# TXB0104_breakout.net
KiCad netlist of a schematic drawn in EAGLE
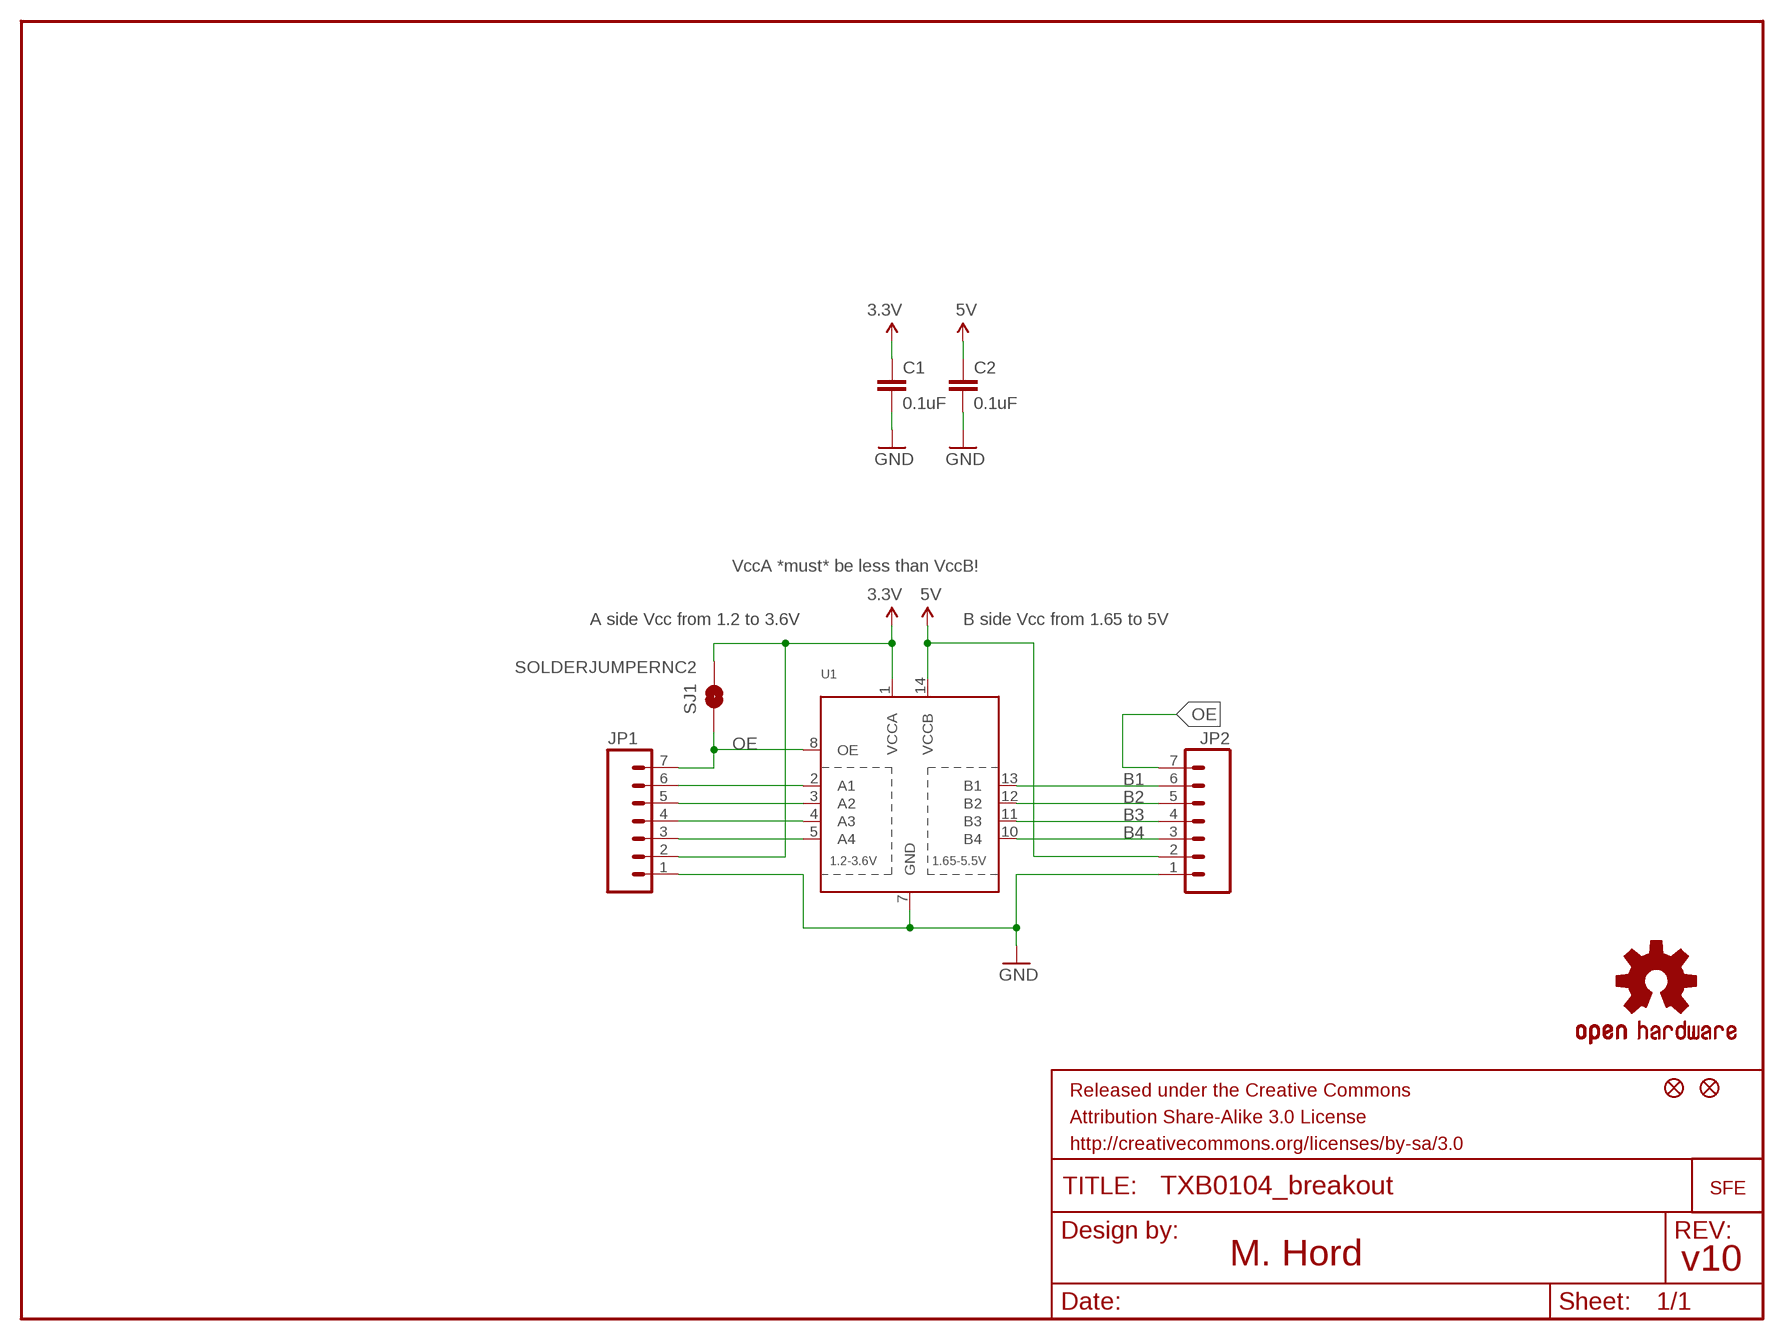
[diagram p0: schematic, sheet 1]

(export (version "E")
  (design (tool "Eeschema 10.0.6"))
  (components
    (comp (ref "C1")
      (value "0.1uF")
      (footprint "eagle-import:0603-CAP")
      (libsource (lib "eagle-import") (part "0.1UF-25V(+80/-20%)(0603)"))
    )
    (comp (ref "C2")
      (value "0.1uF")
      (footprint "eagle-import:0603-CAP")
      (libsource (lib "eagle-import") (part "0.1UF-25V(+80/-20%)(0603)"))
    )
    (comp (ref "FID1")
      (value "FIDUCIALUFIDUCIAL")
      (footprint "eagle-import:MICRO-FIDUCIAL")
      (libsource (lib "eagle-import") (part "FIDUCIALUFIDUCIAL"))
    )
    (comp (ref "FID2")
      (value "FIDUCIALUFIDUCIAL")
      (footprint "eagle-import:MICRO-FIDUCIAL")
      (libsource (lib "eagle-import") (part "FIDUCIALUFIDUCIAL"))
    )
    (comp (ref "FRAME1")
      (value "FRAME-LETTER")
      (footprint "eagle-import:CREATIVE_COMMONS")
      (libsource (lib "eagle-import") (part "FRAME-LETTER"))
    )
    (comp (ref "JP1")
      (value "M07")
      (footprint "eagle-import:1X07")
      (libsource (lib "eagle-import") (part "M07"))
    )
    (comp (ref "JP2")
      (value "M07")
      (footprint "eagle-import:1X07")
      (libsource (lib "eagle-import") (part "M07"))
    )
    (comp (ref "LOGO1")
      (value "LOGO-SFESK")
      (footprint "eagle-import:SFE-LOGO-FLAME")
      (libsource (lib "eagle-import") (part "LOGO-SFESK"))
    )
    (comp (ref "LOGO2")
      (value "OSHW-LOGOS")
      (footprint "eagle-import:OSHW-LOGO-S")
      (libsource (lib "eagle-import") (part "OSHW-LOGOS"))
    )
    (comp (ref "SJ1")
      (value "SOLDERJUMPERNC2")
      (footprint "eagle-import:SJ_2S-NOTRACE")
      (libsource (lib "eagle-import") (part "SOLDERJUMPERNC2"))
    )
    (comp (ref "U1")
      (value "TXB0104PWRSOIC14")
      (footprint "eagle-import:SO14")
      (libsource (lib "eagle-import") (part "TXB0104PWRSOIC14"))
    )
  )
  (nets
    (net (code "1") (name "/B1") (class "Default")
      (node (ref "JP2") (pin "6") (pinfunction "6_6") (pintype "passive"))
      (node (ref "U1") (pin "13") (pinfunction "B1_13") (pintype "bidirectional"))
    )
    (net (code "2") (name "/B2") (class "Default")
      (node (ref "JP2") (pin "5") (pinfunction "5_5") (pintype "passive"))
      (node (ref "U1") (pin "12") (pinfunction "B2_12") (pintype "bidirectional"))
    )
    (net (code "3") (name "/B3") (class "Default")
      (node (ref "JP2") (pin "4") (pinfunction "4_4") (pintype "passive"))
      (node (ref "U1") (pin "11") (pinfunction "B3_11") (pintype "bidirectional"))
    )
    (net (code "4") (name "/B4") (class "Default")
      (node (ref "JP2") (pin "3") (pinfunction "3_3") (pintype "passive"))
      (node (ref "U1") (pin "10") (pinfunction "B4_10") (pintype "bidirectional"))
    )
    (net (code "5") (name "3.3V") (class "Default")
      (node (ref "C1") (pin "1") (pinfunction "1_1") (pintype "passive"))
      (node (ref "JP1") (pin "2") (pinfunction "2_2") (pintype "passive"))
      (node (ref "SJ1") (pin "2") (pinfunction "2_2") (pintype "passive"))
      (node (ref "U1") (pin "1") (pinfunction "VCCA_1") (pintype "bidirectional"))
    )
    (net (code "6") (name "5V") (class "Default")
      (node (ref "C2") (pin "1") (pinfunction "1_1") (pintype "passive"))
      (node (ref "JP2") (pin "2") (pinfunction "2_2") (pintype "passive"))
      (node (ref "U1") (pin "14") (pinfunction "VCCB_14") (pintype "bidirectional"))
    )
    (net (code "7") (name "GND") (class "Default")
      (node (ref "C1") (pin "2") (pinfunction "2_2") (pintype "passive"))
      (node (ref "C2") (pin "2") (pinfunction "2_2") (pintype "passive"))
      (node (ref "JP1") (pin "1") (pinfunction "1_1") (pintype "passive"))
      (node (ref "JP2") (pin "1") (pinfunction "1_1") (pintype "passive"))
      (node (ref "U1") (pin "7") (pinfunction "GND_7") (pintype "bidirectional"))
    )
    (net (code "8") (name "Net-(U1-A1)") (class "Default")
      (node (ref "JP1") (pin "6") (pinfunction "6_6") (pintype "passive"))
      (node (ref "U1") (pin "2") (pinfunction "A1_2") (pintype "bidirectional"))
    )
    (net (code "9") (name "Net-(U1-A2)") (class "Default")
      (node (ref "JP1") (pin "5") (pinfunction "5_5") (pintype "passive"))
      (node (ref "U1") (pin "3") (pinfunction "A2_3") (pintype "bidirectional"))
    )
    (net (code "10") (name "Net-(U1-A3)") (class "Default")
      (node (ref "JP1") (pin "4") (pinfunction "4_4") (pintype "passive"))
      (node (ref "U1") (pin "4") (pinfunction "A3_4") (pintype "bidirectional"))
    )
    (net (code "11") (name "Net-(U1-A4)") (class "Default")
      (node (ref "JP1") (pin "3") (pinfunction "3_3") (pintype "passive"))
      (node (ref "U1") (pin "5") (pinfunction "A4_5") (pintype "bidirectional"))
    )
    (net (code "12") (name "OE") (class "Default")
      (node (ref "JP1") (pin "7") (pinfunction "7_7") (pintype "passive"))
      (node (ref "JP2") (pin "7") (pinfunction "7_7") (pintype "passive"))
      (node (ref "SJ1") (pin "1") (pinfunction "1_1") (pintype "passive"))
      (node (ref "U1") (pin "8") (pinfunction "OE_8") (pintype "bidirectional"))
    )
  )
)
